# 1-Schematic_passcipher.net
KiCad netlist of a schematic drawn in EasyEDA
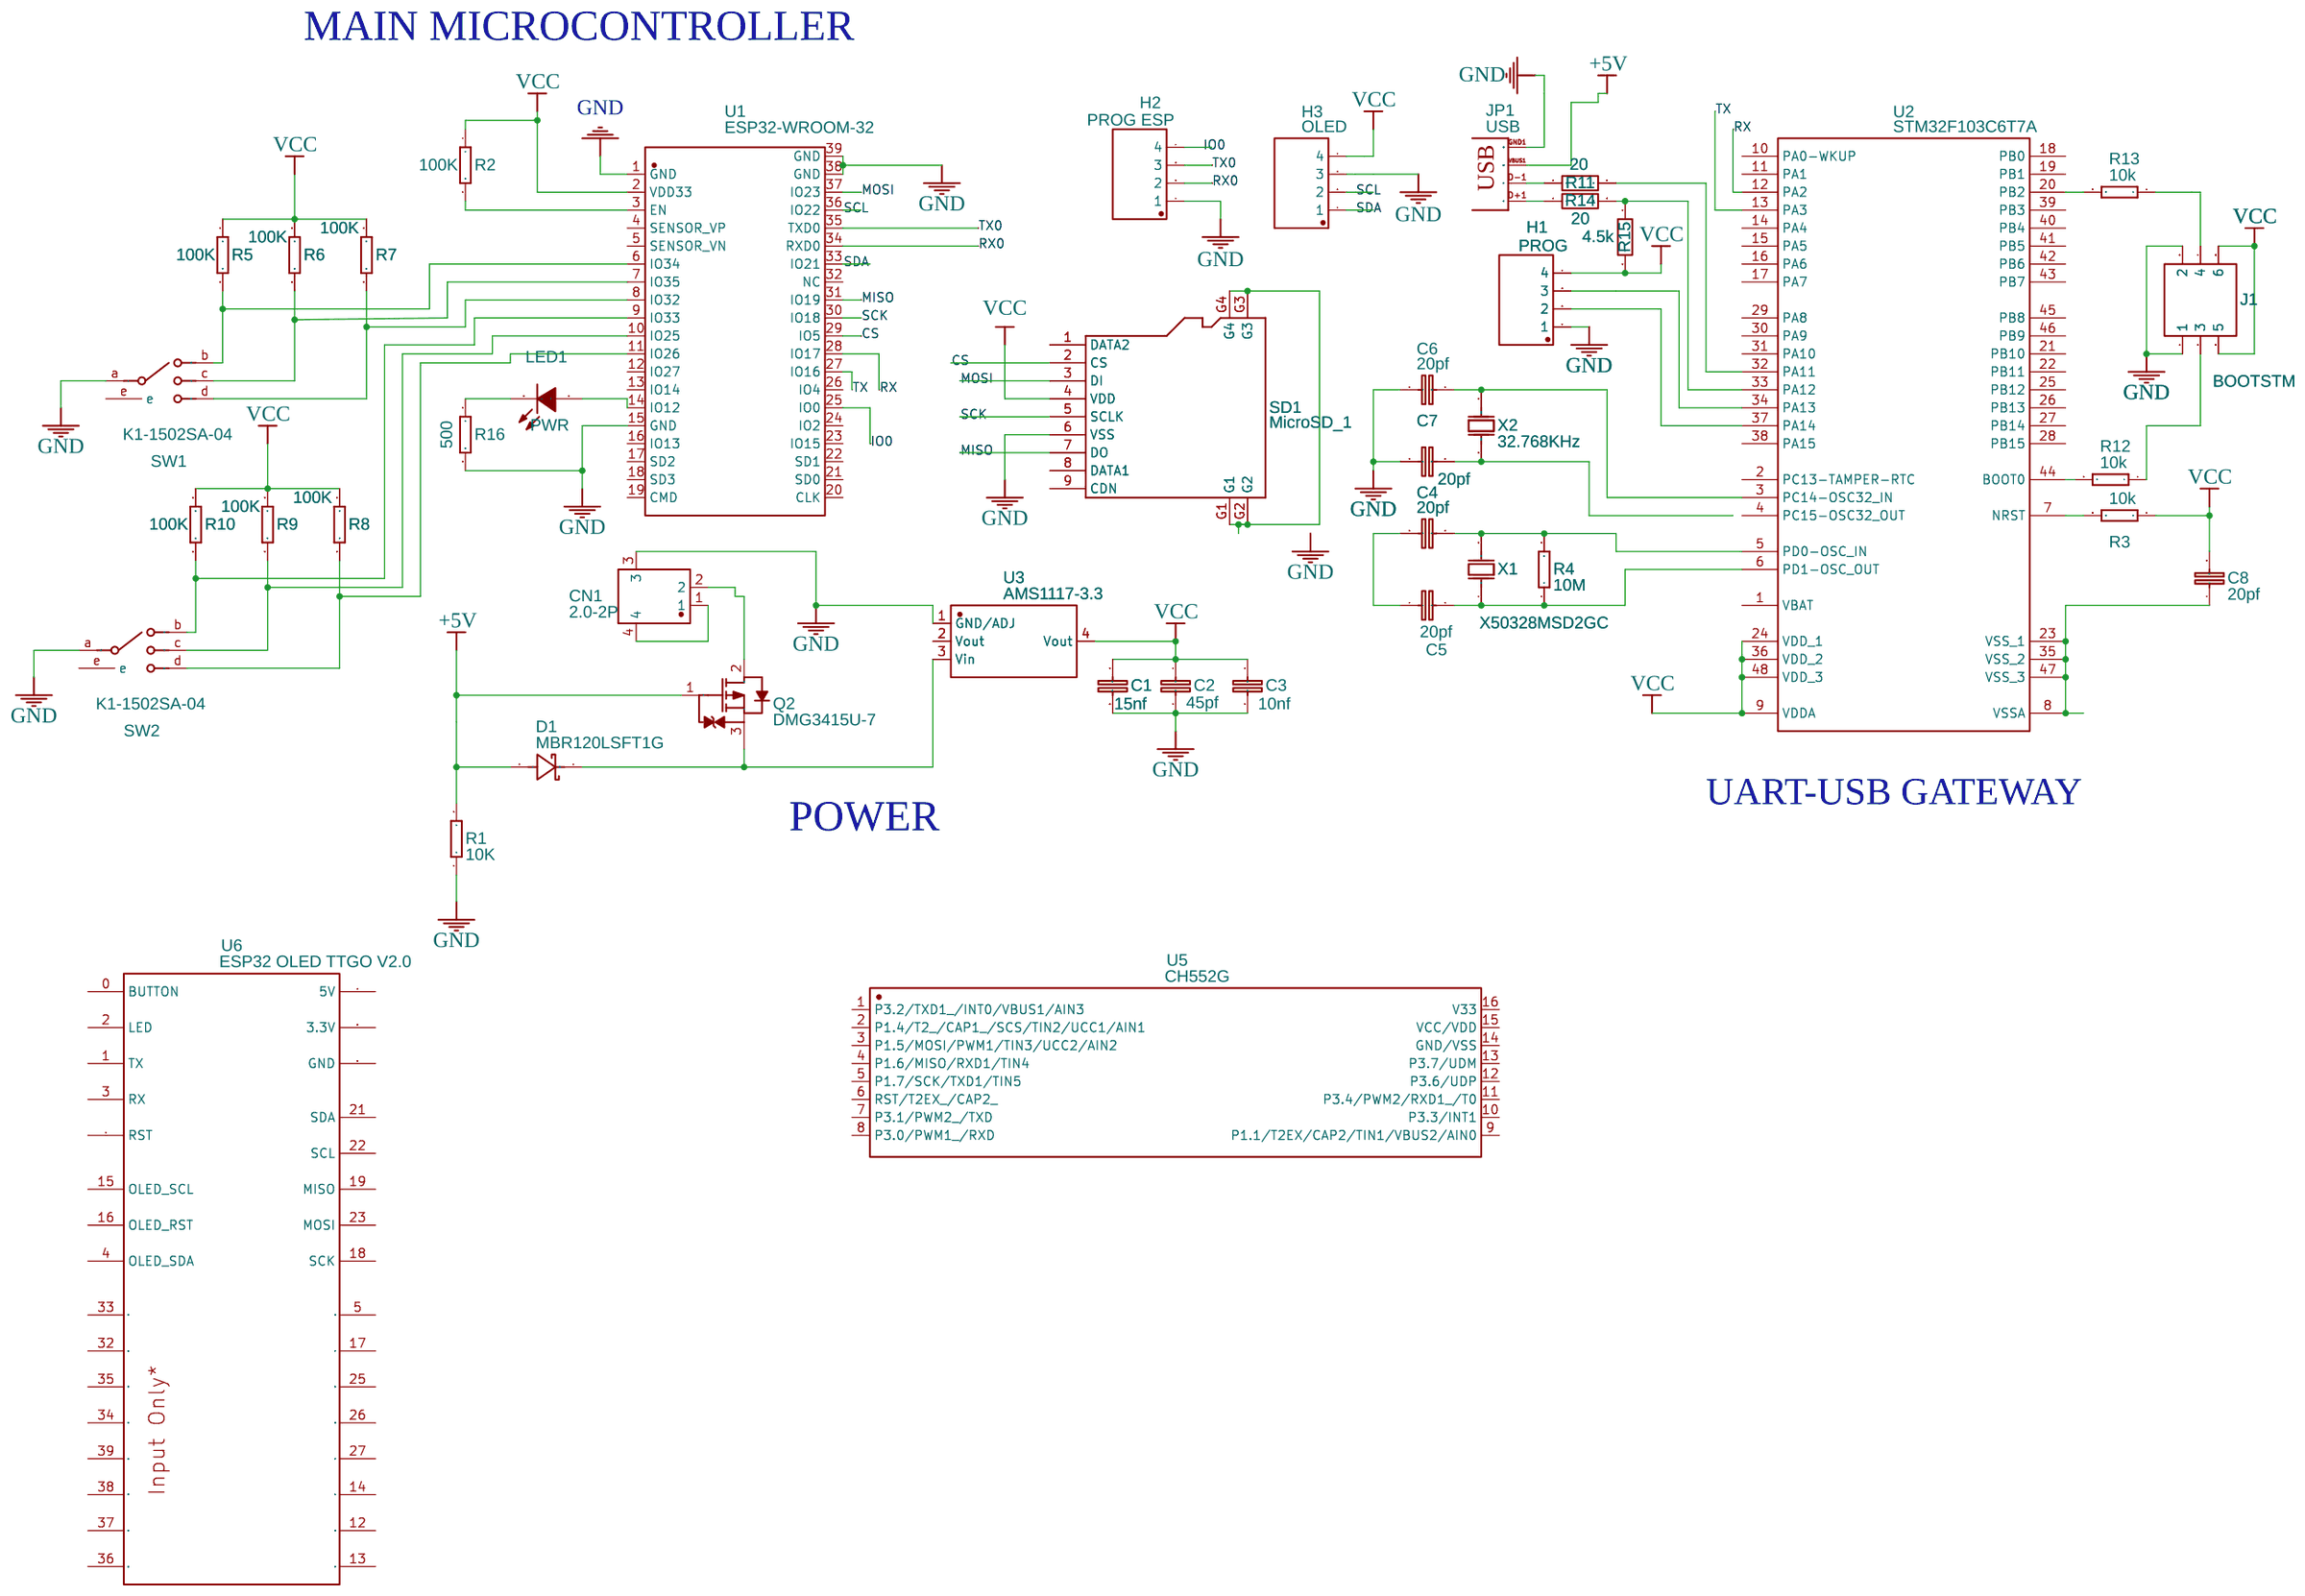
[diagram p0: Sheet_1]
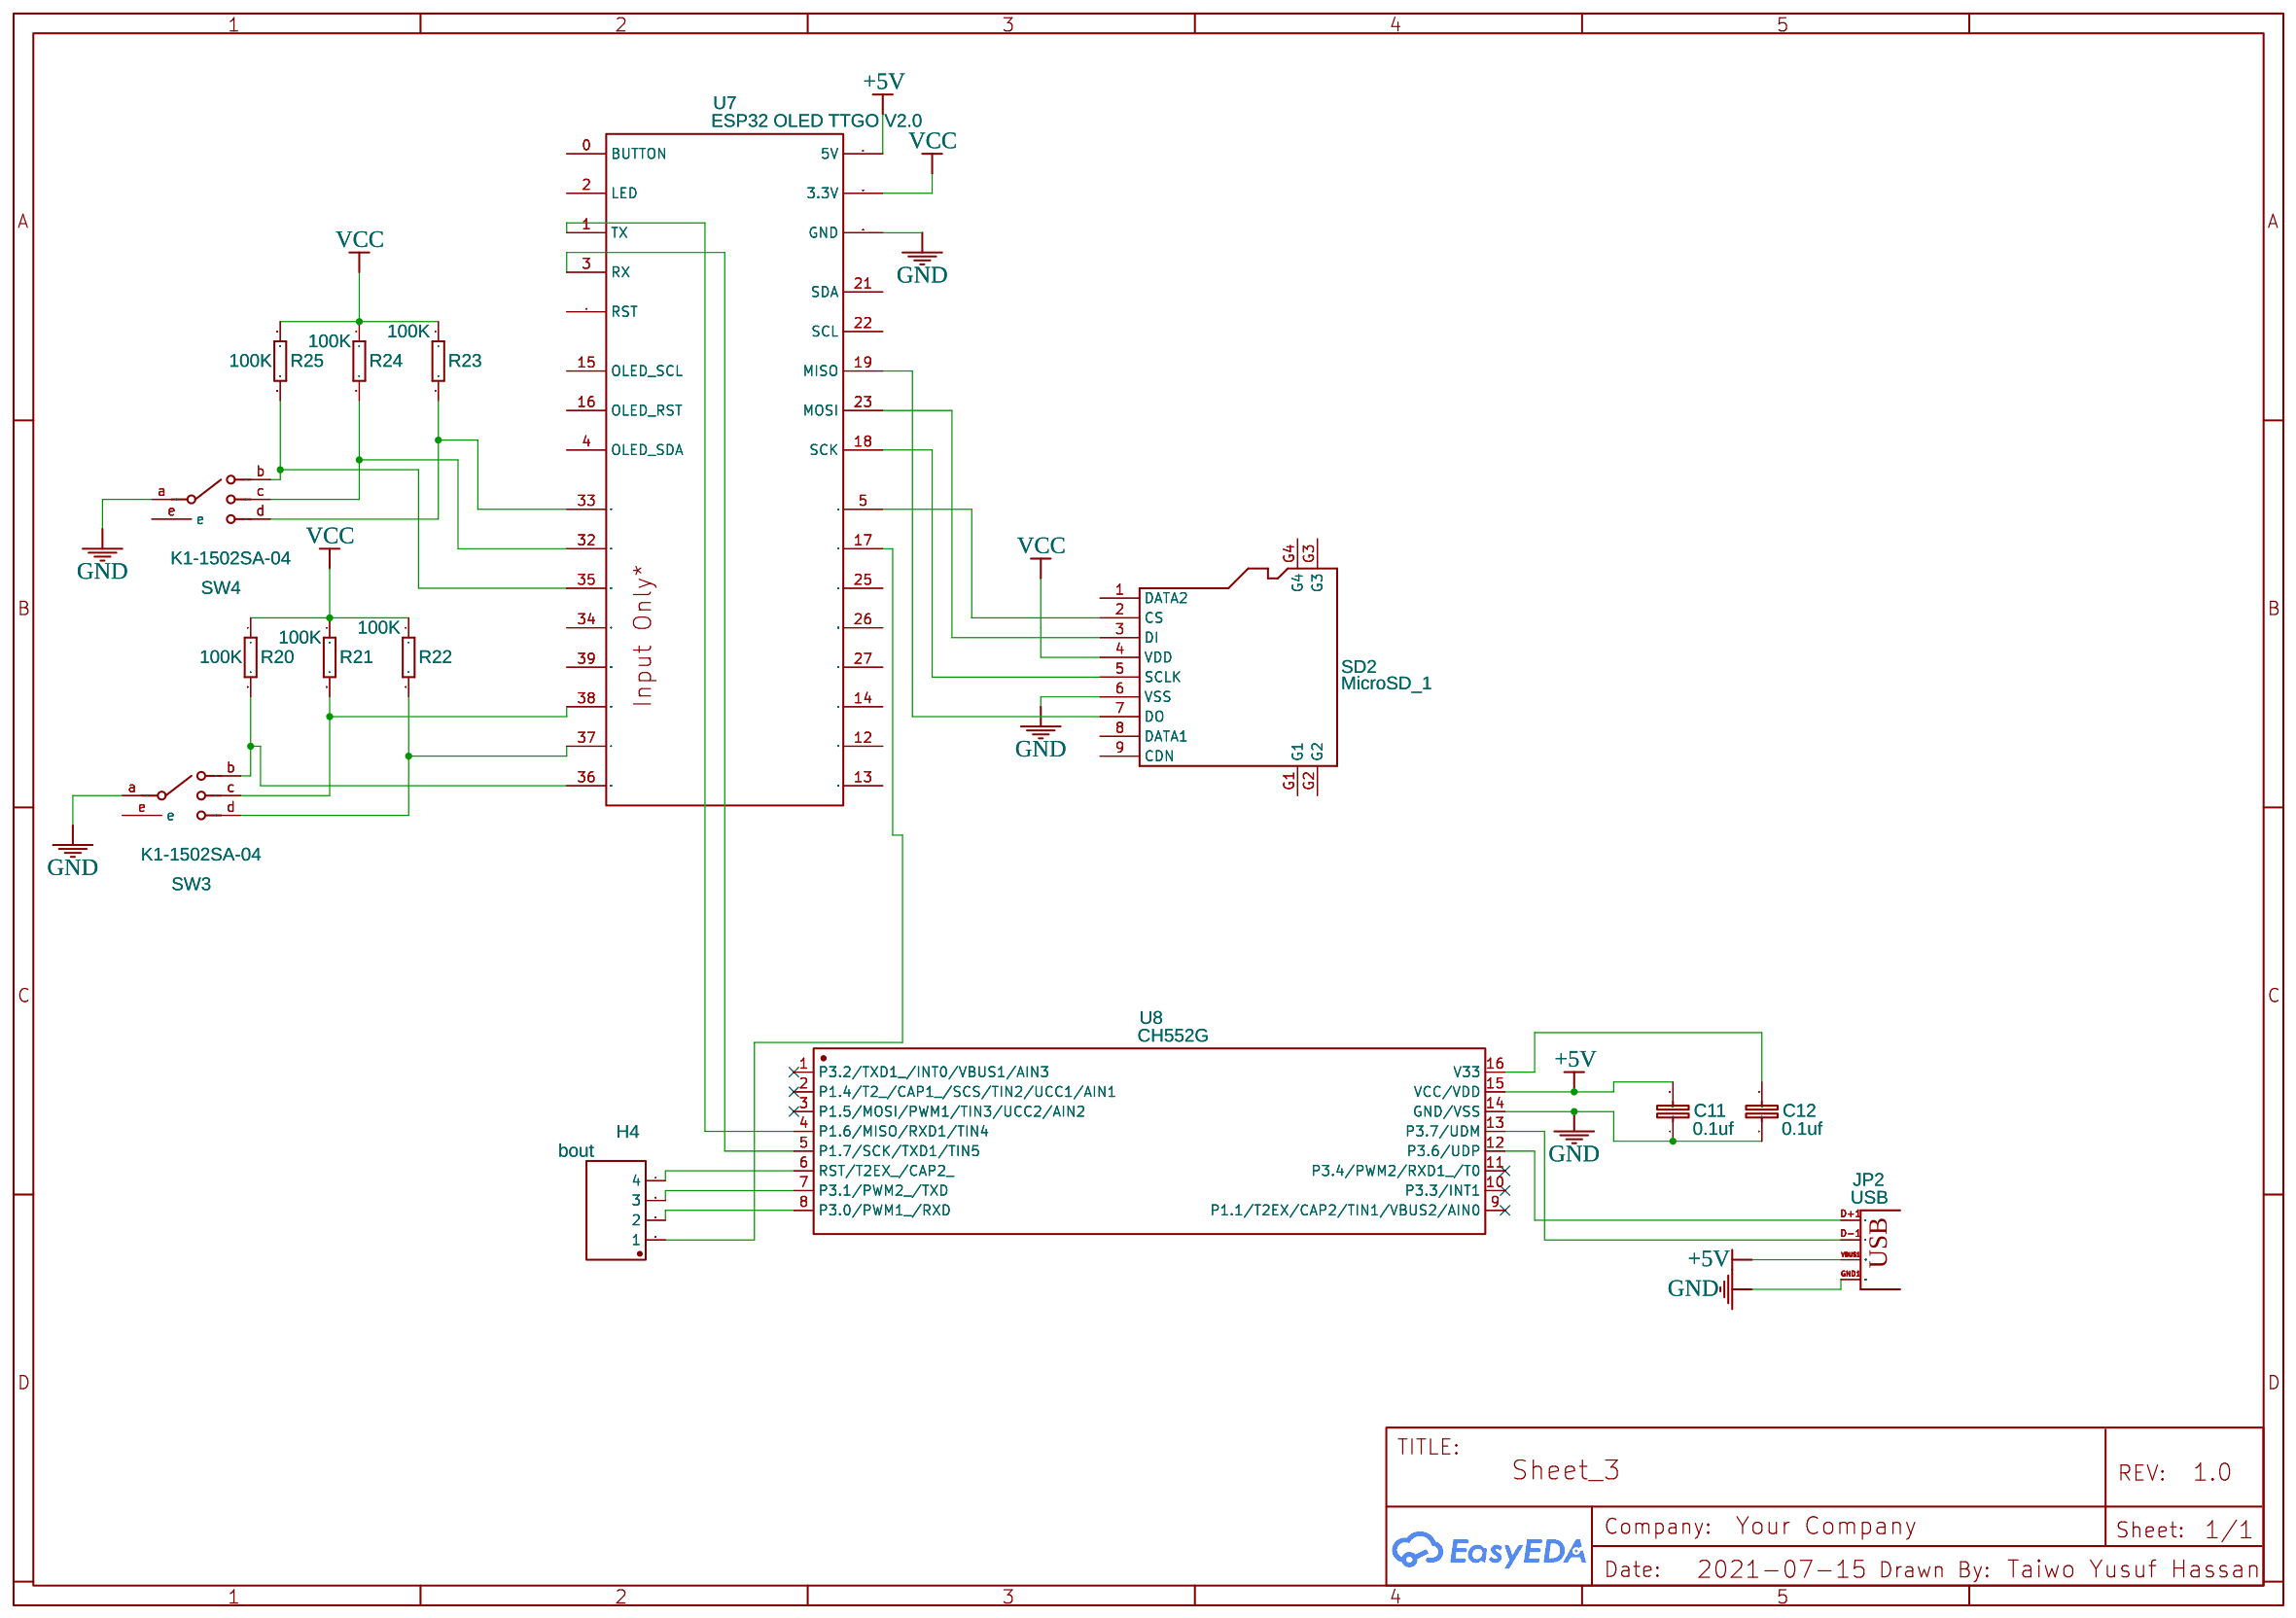
[diagram p1: expansionboard]

(export (version "E")
  (design (tool "Eeschema 10.0.6"))
  (components
    (comp (ref "C1") (value "15nf") (libsource (lib "") (part "CAPACITOR_NPOL_1")))
    (comp (ref "C2") (value "45pf") (libsource (lib "") (part "CAPACITOR_NPOL_1")))
    (comp (ref "C3") (value "10nf") (libsource (lib "") (part "CAPACITOR_NPOL_1")))
    (comp (ref "C4") (value "20pf") (libsource (lib "") (part "CAPACITOR_NPOL")))
    (comp (ref "C5") (value "20pf") (libsource (lib "") (part "CAPACITOR_NPOL")))
    (comp (ref "C6") (value "20pf") (libsource (lib "") (part "CAPACITOR_NPOL")))
    (comp (ref "C7") (value "20pf") (libsource (lib "") (part "CAPACITOR_NPOL")))
    (comp (ref "C8") (value "20pf") (libsource (lib "") (part "CAPACITOR_NPOL_2")))
    (comp (ref "CN1")
      (value "2.0-2P")
      (fields (field (name "BOM_Supplier Part") "C146053"))
      (libsource (lib "") (part "2.0-2P"))
    )
    (comp (ref "D1")
      (value "MBR120LSFT1G")
      (fields (field (name "BOM_Supplier Part") "C891416"))
      (libsource (lib "") (part "MBR120LSFT1G"))
    )
    (comp (ref "H1")
      (value "PROG")
      (fields
        (field (name "BOM_Manufacturer Part") "210S-1*4P L=11.6MMGold-plated black")
        (field (name "BOM_Supplier Part") "C124378")
      )
      (libsource (lib "") (part "Header-Male-2.54_1x4"))
    )
    (comp (ref "H2")
      (value "PROG ESP")
      (fields
        (field (name "BOM_Manufacturer Part") "210S-1*4P L=11.6MMGold-plated black")
        (field (name "BOM_Supplier Part") "C124378")
      )
      (libsource (lib "") (part "Header-Male-2.54_1x4"))
    )
    (comp (ref "H3")
      (value "OLED")
      (fields
        (field (name "BOM_Manufacturer Part") "210S-1*4P L=11.6MMGold-plated black")
        (field (name "BOM_Supplier Part") "C124378")
      )
      (libsource (lib "") (part "Header-Male-2.54_1x4"))
    )
    (comp (ref "J1")
      (value "BOOTSTM")
      (fields
        (field (name "BOM_Manufacturer Part") "Header-Male-2.54_2x3")
        (field (name "BOM_Supplier Part") "C65114")
      )
      (libsource (lib "") (part "Header-Male-2.54_2x3"))
    )
    (comp (ref "JP1") (value "USB") (libsource (lib "") (part "USB")))
    (comp (ref "LED1")
      (value "PWR")
      (fields
        (field (name "BOM_Manufacturer Part") "LTST-C193TGKT-5A")
        (field (name "BOM_Supplier Part") "C12065")
      )
      (libsource (lib "") (part "LTST-C193TGKT-5A"))
    )
    (comp (ref "Q2")
      (value "DMG3415U-7")
      (fields (field (name "BOM_Supplier Part") "C96616"))
      (libsource (lib "") (part "DMG3415U-7"))
    )
    (comp (ref "R1") (value "10K") (libsource (lib "") (part "RESISTOR_2")))
    (comp (ref "R2") (value "100K") (libsource (lib "") (part "RESISTOR_1")))
    (comp (ref "R3") (value "10k") (libsource (lib "") (part "RESISTOR")))
    (comp (ref "R4") (value "10M") (libsource (lib "") (part "RESISTOR_2")))
    (comp (ref "R5") (value "100K") (libsource (lib "") (part "RESISTOR_1")))
    (comp (ref "R6") (value "100K") (libsource (lib "") (part "RESISTOR_1")))
    (comp (ref "R7") (value "100K") (libsource (lib "") (part "RESISTOR_1")))
    (comp (ref "R8") (value "100K") (libsource (lib "") (part "RESISTOR_1")))
    (comp (ref "R9") (value "100K") (libsource (lib "") (part "RESISTOR_1")))
    (comp (ref "R10") (value "100K") (libsource (lib "") (part "RESISTOR_1")))
    (comp (ref "R11")
      (value "20")
      (fields
        (field (name "BOM_Manufacturer Part") "RS-03K3242FT")
        (field (name "BOM_Supplier Part") "C304734")
      )
      (libsource (lib "") (part "RS-03K3242FT_1"))
    )
    (comp (ref "R12") (value "10k") (libsource (lib "") (part "RESISTOR")))
    (comp (ref "R13") (value "10k") (libsource (lib "") (part "RESISTOR")))
    (comp (ref "R14")
      (value "20")
      (fields
        (field (name "BOM_Manufacturer Part") "RS-03K3242FT")
        (field (name "BOM_Supplier Part") "C304734")
      )
      (libsource (lib "") (part "RS-03K3242FT_1"))
    )
    (comp (ref "R15")
      (value "4.5k")
      (fields
        (field (name "BOM_Manufacturer Part") "RS-03K3242FT")
        (field (name "BOM_Supplier Part") "C304734")
      )
      (libsource (lib "") (part "RS-03K3242FT"))
    )
    (comp (ref "R16") (value "500") (libsource (lib "") (part "RESISTOR_1")))
    (comp (ref "SD1")
      (value "MicroSD_1")
      (fields (field (name "BOM_Manufacturer Part") "?") (field (name "BOM_Supplier Part") "320090008"))
      (libsource (lib "") (part "MicroSD_1"))
    )
    (comp (ref "SW1")
      (value "K1-1502SA-04")
      (fields (field (name "BOM_Supplier Part") "C145914"))
      (libsource (lib "") (part "K1-1502SA-04"))
    )
    (comp (ref "SW2")
      (value "K1-1502SA-04")
      (fields (field (name "BOM_Supplier Part") "C145914"))
      (libsource (lib "") (part "K1-1502SA-04"))
    )
    (comp (ref "U1")
      (value "ESP32-WROOM-32")
      (fields (field (name "BOM_Supplier Part") "C503587"))
      (libsource (lib "") (part "ESP32-WROOM-32"))
    )
    (comp (ref "U2")
      (value "STM32F103C6T7A")
      (fields (field (name "BOM_Supplier Part") "C222074"))
      (libsource (lib "") (part "STM32F103C6T7A"))
    )
    (comp (ref "U3")
      (value "AMS1117-3.3")
      (fields (field (name "BOM_Supplier Part") "C6186"))
      (libsource (lib "") (part "AMS1117-3.3"))
    )
    (comp (ref "U5")
      (value "CH552G")
      (fields (field (name "BOM_Supplier Part") "C111292"))
      (libsource (lib "") (part "CH552G"))
    )
    (comp (ref "U6")
      (value "ESP32 OLED TTGO V2.0")
      (fields
        (field (name "BOM_Manufacturer Part") "ESP32 OLED TTGO V2.0 Pro")
        (field (name "BOM_Supplier Part") "32822105291")
      )
      (libsource (lib "") (part "ESP32 OLED TTGO V2.0"))
    )
    (comp (ref "X1")
      (value "X50328MSD2GC")
      (fields (field (name "BOM_Supplier Part") "C18560"))
      (libsource (lib "") (part "X50328MSD2GC"))
    )
    (comp (ref "X2")
      (value "32.768KHz")
      (fields
        (field (name "BOM_Manufacturer Part") "9H0322LCSC-DZF2S")
        (field (name "BOM_Supplier Part") "C90943")
      )
      (libsource (lib "") (part "9H0322LCSC-DZF2S"))
    )
    (comp (ref "C11") (value "0.1uf") (libsource (lib "") (part "CAPACITOR_NPOL")))
    (comp (ref "C12") (value "0.1uf") (libsource (lib "") (part "CAPACITOR_NPOL")))
    (comp (ref "H4")
      (value "bout")
      (fields
        (field (name "BOM_Manufacturer Part") "210S-1*4P L=11.6MMGold-plated black")
        (field (name "BOM_Supplier Part") "C124378")
      )
      (libsource (lib "") (part "Header-Male-2.54_1x4"))
    )
    (comp (ref "JP2") (value "USB") (libsource (lib "") (part "USB")))
    (comp (ref "R20") (value "100K") (libsource (lib "") (part "RESISTOR")))
    (comp (ref "R21") (value "100K") (libsource (lib "") (part "RESISTOR")))
    (comp (ref "R22") (value "100K") (libsource (lib "") (part "RESISTOR")))
    (comp (ref "R23") (value "100K") (libsource (lib "") (part "RESISTOR")))
    (comp (ref "R24") (value "100K") (libsource (lib "") (part "RESISTOR")))
    (comp (ref "R25") (value "100K") (libsource (lib "") (part "RESISTOR")))
    (comp (ref "SD2")
      (value "MicroSD_1")
      (fields (field (name "BOM_Manufacturer Part") "?") (field (name "BOM_Supplier Part") "320090008"))
      (libsource (lib "") (part "MicroSD_1"))
    )
    (comp (ref "SW3")
      (value "K1-1502SA-04")
      (fields (field (name "BOM_Supplier Part") "C145914"))
      (libsource (lib "") (part "K1-1502SA-04"))
    )
    (comp (ref "SW4")
      (value "K1-1502SA-04")
      (fields (field (name "BOM_Supplier Part") "C145914"))
      (libsource (lib "") (part "K1-1502SA-04"))
    )
    (comp (ref "U7")
      (value "ESP32 OLED TTGO V2.0")
      (fields
        (field (name "BOM_Manufacturer Part") "ESP32 OLED TTGO V2.0 Pro")
        (field (name "BOM_Supplier Part") "32822105291")
      )
      (libsource (lib "") (part "ESP32 OLED TTGO V2.0"))
    )
    (comp (ref "U8")
      (value "CH552G")
      (fields (field (name "BOM_Supplier Part") "C111292"))
      (libsource (lib "") (part "CH552G"))
    )
  )
  (nets
    (net (code "1") (name "+5V") (class "Default")
      (node (ref "C11") (pin "2") (pinfunction "2_2") (pintype "unspecified"))
      (node (ref "D1") (pin "2") (pinfunction "A_2") (pintype "unspecified"))
      (node (ref "JP1") (pin "VBUS1") (pinfunction "VBUS_VBUS1") (pintype "unspecified"))
      (node (ref "JP2") (pin "VBUS1") (pinfunction "VBUS_VBUS1") (pintype "unspecified"))
      (node (ref "Q2") (pin "1") (pinfunction "G_1") (pintype "unspecified"))
      (node (ref "R1") (pin "2") (pinfunction "2_2") (pintype "unspecified"))
      (node (ref "U7") (pin "41") (pinfunction "5V_41") (pintype "unspecified"))
      (node (ref "U8") (pin "15") (pinfunction "VCC/VDD_15") (pintype "unspecified"))
    )
    (net (code "2") (name "CS") (class "Default")
      (node (ref "SD1") (pin "2") (pinfunction "CS_2") (pintype "unspecified"))
      (node (ref "U1") (pin "29") (pinfunction "IO5_29") (pintype "unspecified"))
    )
    (net (code "3") (name "GND") (class "Default")
      (node (ref "C1") (pin "2") (pinfunction "2_2") (pintype "unspecified"))
      (node (ref "C11") (pin "1") (pinfunction "1_1") (pintype "unspecified"))
      (node (ref "C12") (pin "1") (pinfunction "1_1") (pintype "unspecified"))
      (node (ref "C2") (pin "2") (pinfunction "2_2") (pintype "unspecified"))
      (node (ref "C3") (pin "2") (pinfunction "2_2") (pintype "unspecified"))
      (node (ref "C6") (pin "1") (pinfunction "1_1") (pintype "unspecified"))
      (node (ref "C7") (pin "1") (pinfunction "1_1") (pintype "unspecified"))
      (node (ref "CN1") (pin "3") (pinfunction "3_3") (pintype "unspecified"))
      (node (ref "H1") (pin "1") (pinfunction "1_1") (pintype "unspecified"))
      (node (ref "H2") (pin "1") (pinfunction "1_1") (pintype "unspecified"))
      (node (ref "H3") (pin "3") (pinfunction "3_3") (pintype "unspecified"))
      (node (ref "J1") (pin "1") (pinfunction "1_1") (pintype "input"))
      (node (ref "J1") (pin "2") (pinfunction "2_2") (pintype "input"))
      (node (ref "JP1") (pin "GND1") (pinfunction "GND_GND1") (pintype "unspecified"))
      (node (ref "JP2") (pin "GND1") (pinfunction "GND_GND1") (pintype "unspecified"))
      (node (ref "R1") (pin "1") (pinfunction "1_1") (pintype "unspecified"))
      (node (ref "R16") (pin "2") (pinfunction "2_2") (pintype "unspecified"))
      (node (ref "SD1") (pin "6") (pinfunction "VSS_6") (pintype "unspecified"))
      (node (ref "SD2") (pin "6") (pinfunction "VSS_6") (pintype "unspecified"))
      (node (ref "SW1") (pin "a") (pinfunction "a_a") (pintype "unspecified"))
      (node (ref "SW2") (pin "a") (pinfunction "a_a") (pintype "unspecified"))
      (node (ref "SW3") (pin "a") (pinfunction "a_a") (pintype "unspecified"))
      (node (ref "SW4") (pin "a") (pinfunction "a_a") (pintype "unspecified"))
      (node (ref "U1") (pin "1") (pinfunction "GND_1") (pintype "unspecified"))
      (node (ref "U1") (pin "15") (pinfunction "GND_15") (pintype "unspecified"))
      (node (ref "U1") (pin "38") (pinfunction "GND_38") (pintype "unspecified"))
      (node (ref "U1") (pin "39") (pinfunction "GND_39") (pintype "unspecified"))
      (node (ref "U3") (pin "1") (pinfunction "GND/ADJ_1") (pintype "unspecified"))
      (node (ref "U7") (pin "40") (pinfunction "GND_40") (pintype "unspecified"))
      (node (ref "U8") (pin "14") (pinfunction "GND/VSS_14") (pintype "unspecified"))
    )
    (net (code "4") (name "IO0") (class "Default")
      (node (ref "H2") (pin "4") (pinfunction "4_4") (pintype "unspecified"))
      (node (ref "U1") (pin "25") (pinfunction "IO0_25") (pintype "unspecified"))
    )
    (net (code "5") (name "MISO") (class "Default")
      (node (ref "SD1") (pin "7") (pinfunction "DO_7") (pintype "unspecified"))
      (node (ref "U1") (pin "31") (pinfunction "IO19_31") (pintype "unspecified"))
    )
    (net (code "6") (name "MOSI") (class "Default")
      (node (ref "SD1") (pin "3") (pinfunction "DI_3") (pintype "unspecified"))
      (node (ref "U1") (pin "37") (pinfunction "IO23_37") (pintype "unspecified"))
    )
    (net (code "7") (name "Net-(C4-Pad1)") (class "Default")
      (node (ref "C4") (pin "1") (pinfunction "1_1") (pintype "unspecified"))
      (node (ref "C5") (pin "1") (pinfunction "1_1") (pintype "unspecified"))
    )
    (net (code "8") (name "Net-(CN1-Pad1)") (class "Default")
      (node (ref "CN1") (pin "1") (pinfunction "1_1") (pintype "unspecified"))
      (node (ref "CN1") (pin "4") (pinfunction "4_4") (pintype "unspecified"))
    )
    (net (code "9") (name "Net-(D1-C)") (class "Default")
      (node (ref "D1") (pin "1") (pinfunction "C_1") (pintype "unspecified"))
      (node (ref "Q2") (pin "3") (pinfunction "S_3") (pintype "unspecified"))
      (node (ref "U3") (pin "3") (pinfunction "Vin_3") (pintype "unspecified"))
    )
    (net (code "10") (name "Net-(H4-Pad1)") (class "Default")
      (node (ref "H4") (pin "1") (pinfunction "1_1") (pintype "unspecified"))
      (node (ref "U7") (pin "17") (pinfunction "17_17") (pintype "unspecified"))
    )
    (net (code "11") (name "Net-(J1-Pad3)") (class "Default")
      (node (ref "J1") (pin "3") (pinfunction "3_3") (pintype "input"))
      (node (ref "R12") (pin "1") (pinfunction "1_1") (pintype "unspecified"))
    )
    (net (code "12") (name "Net-(J1-Pad4)") (class "Default")
      (node (ref "J1") (pin "4") (pinfunction "4_4") (pintype "input"))
      (node (ref "R13") (pin "1") (pinfunction "1_1") (pintype "unspecified"))
    )
    (net (code "13") (name "Net-(JP1-D+)") (class "Default")
      (node (ref "JP1") (pin "D+1") (pinfunction "D+_D+1") (pintype "unspecified"))
      (node (ref "R14") (pin "1") (pinfunction "1_1") (pintype "unspecified"))
    )
    (net (code "14") (name "Net-(JP1-D-)") (class "Default")
      (node (ref "JP1") (pin "D-1") (pinfunction "D-_D-1") (pintype "unspecified"))
      (node (ref "R11") (pin "1") (pinfunction "1_1") (pintype "unspecified"))
    )
    (net (code "15") (name "Net-(JP2-D+)") (class "Default")
      (node (ref "JP2") (pin "D+1") (pinfunction "D+_D+1") (pintype "unspecified"))
      (node (ref "U8") (pin "12") (pinfunction "P3.6/UDP_12") (pintype "unspecified"))
    )
    (net (code "16") (name "Net-(JP2-D-)") (class "Default")
      (node (ref "JP2") (pin "D-1") (pinfunction "D-_D-1") (pintype "unspecified"))
      (node (ref "U8") (pin "13") (pinfunction "P3.7/UDM_13") (pintype "unspecified"))
    )
    (net (code "17") (name "Net-(LED1-A)") (class "Default")
      (node (ref "LED1") (pin "1") (pinfunction "A_1") (pintype "unspecified"))
      (node (ref "U1") (pin "14") (pinfunction "IO12_14") (pintype "unspecified"))
    )
    (net (code "18") (name "Net-(LED1-K)") (class "Default")
      (node (ref "LED1") (pin "2") (pinfunction "K_2") (pintype "unspecified"))
      (node (ref "R16") (pin "1") (pinfunction "1_1") (pintype "unspecified"))
    )
    (net (code "19") (name "Net-(Q2-D)") (class "Default")
      (node (ref "CN1") (pin "2") (pinfunction "2_2") (pintype "unspecified"))
      (node (ref "Q2") (pin "2") (pinfunction "D_2") (pintype "unspecified"))
    )
    (net (code "20") (name "Net-(R20-Pad2)") (class "Default")
      (node (ref "R20") (pin "2") (pinfunction "2_2") (pintype "unspecified"))
      (node (ref "SW3") (pin "b") (pinfunction "b_b") (pintype "unspecified"))
      (node (ref "U7") (pin "36") (pinfunction "36_36") (pintype "unspecified"))
    )
    (net (code "21") (name "Net-(R21-Pad2)") (class "Default")
      (node (ref "R21") (pin "2") (pinfunction "2_2") (pintype "unspecified"))
      (node (ref "SW3") (pin "c") (pinfunction "c_c") (pintype "unspecified"))
      (node (ref "U7") (pin "38") (pinfunction "38_38") (pintype "unspecified"))
    )
    (net (code "22") (name "Net-(R22-Pad2)") (class "Default")
      (node (ref "R22") (pin "2") (pinfunction "2_2") (pintype "unspecified"))
      (node (ref "SW3") (pin "d") (pinfunction "d_d") (pintype "unspecified"))
      (node (ref "U7") (pin "37") (pinfunction "37_37") (pintype "unspecified"))
    )
    (net (code "23") (name "Net-(R23-Pad2)") (class "Default")
      (node (ref "R23") (pin "2") (pinfunction "2_2") (pintype "unspecified"))
      (node (ref "SW4") (pin "d") (pinfunction "d_d") (pintype "unspecified"))
      (node (ref "U7") (pin "33") (pinfunction "33_33") (pintype "unspecified"))
    )
    (net (code "24") (name "Net-(R24-Pad2)") (class "Default")
      (node (ref "R24") (pin "2") (pinfunction "2_2") (pintype "unspecified"))
      (node (ref "SW4") (pin "c") (pinfunction "c_c") (pintype "unspecified"))
      (node (ref "U7") (pin "32") (pinfunction "32_32") (pintype "unspecified"))
    )
    (net (code "25") (name "Net-(R25-Pad2)") (class "Default")
      (node (ref "R25") (pin "2") (pinfunction "2_2") (pintype "unspecified"))
      (node (ref "SW4") (pin "b") (pinfunction "b_b") (pintype "unspecified"))
      (node (ref "U7") (pin "35") (pinfunction "35_35") (pintype "unspecified"))
    )
    (net (code "26") (name "Net-(SD1-PadG1)") (class "Default")
      (node (ref "SD1") (pin "G1") (pinfunction "G1_G1") (pintype "unspecified"))
      (node (ref "SD1") (pin "G2") (pinfunction "G2_G2") (pintype "unspecified"))
      (node (ref "SD1") (pin "G3") (pinfunction "G3_G3") (pintype "unspecified"))
      (node (ref "SD1") (pin "G4") (pinfunction "G4_G4") (pintype "unspecified"))
    )
    (net (code "27") (name "Net-(SD2-CS)") (class "Default")
      (node (ref "SD2") (pin "2") (pinfunction "CS_2") (pintype "unspecified"))
      (node (ref "U7") (pin "5") (pinfunction "5_5") (pintype "unspecified"))
    )
    (net (code "28") (name "Net-(SD2-DI)") (class "Default")
      (node (ref "SD2") (pin "3") (pinfunction "DI_3") (pintype "unspecified"))
      (node (ref "U7") (pin "23") (pinfunction "MOSI_23") (pintype "unspecified"))
    )
    (net (code "29") (name "Net-(SD2-DO)") (class "Default")
      (node (ref "SD2") (pin "7") (pinfunction "DO_7") (pintype "unspecified"))
      (node (ref "U7") (pin "19") (pinfunction "MISO_19") (pintype "unspecified"))
    )
    (net (code "30") (name "Net-(SD2-SCLK)") (class "Default")
      (node (ref "SD2") (pin "5") (pinfunction "SCLK_5") (pintype "unspecified"))
      (node (ref "U7") (pin "18") (pinfunction "SCK_18") (pintype "unspecified"))
    )
    (net (code "31") (name "Net-(U1-EN)") (class "Default")
      (node (ref "R2") (pin "2") (pinfunction "2_2") (pintype "unspecified"))
      (node (ref "U1") (pin "3") (pinfunction "EN_3") (pintype "unspecified"))
    )
    (net (code "32") (name "Net-(U1-IO25)") (class "Default")
      (node (ref "R9") (pin "2") (pinfunction "2_2") (pintype "unspecified"))
      (node (ref "SW2") (pin "c") (pinfunction "c_c") (pintype "unspecified"))
      (node (ref "U1") (pin "10") (pinfunction "IO25_10") (pintype "unspecified"))
    )
    (net (code "33") (name "Net-(U1-IO26)") (class "Default")
      (node (ref "R8") (pin "2") (pinfunction "2_2") (pintype "unspecified"))
      (node (ref "SW2") (pin "d") (pinfunction "d_d") (pintype "unspecified"))
      (node (ref "U1") (pin "11") (pinfunction "IO26_11") (pintype "unspecified"))
    )
    (net (code "34") (name "Net-(U1-IO32)") (class "Default")
      (node (ref "R7") (pin "2") (pinfunction "2_2") (pintype "unspecified"))
      (node (ref "SW1") (pin "d") (pinfunction "d_d") (pintype "unspecified"))
      (node (ref "U1") (pin "8") (pinfunction "IO32_8") (pintype "unspecified"))
    )
    (net (code "35") (name "Net-(U1-IO33)") (class "Default")
      (node (ref "R10") (pin "2") (pinfunction "2_2") (pintype "unspecified"))
      (node (ref "SW2") (pin "b") (pinfunction "b_b") (pintype "unspecified"))
      (node (ref "U1") (pin "9") (pinfunction "IO33_9") (pintype "unspecified"))
    )
    (net (code "36") (name "Net-(U1-IO34)") (class "Default")
      (node (ref "R5") (pin "2") (pinfunction "2_2") (pintype "unspecified"))
      (node (ref "SW1") (pin "b") (pinfunction "b_b") (pintype "unspecified"))
      (node (ref "U1") (pin "6") (pinfunction "IO34_6") (pintype "unspecified"))
    )
    (net (code "37") (name "Net-(U1-IO35)") (class "Default")
      (node (ref "R6") (pin "2") (pinfunction "2_2") (pintype "unspecified"))
      (node (ref "SW1") (pin "c") (pinfunction "c_c") (pintype "unspecified"))
      (node (ref "U1") (pin "7") (pinfunction "IO35_7") (pintype "unspecified"))
    )
    (net (code "38") (name "Net-(U2-BOOT0)") (class "Default")
      (node (ref "R12") (pin "2") (pinfunction "2_2") (pintype "unspecified"))
      (node (ref "U2") (pin "44") (pinfunction "BOOT0_44") (pintype "unspecified"))
    )
    (net (code "39") (name "Net-(U2-NRST)") (class "Default")
      (node (ref "R3") (pin "2") (pinfunction "2_2") (pintype "unspecified"))
      (node (ref "U2") (pin "7") (pinfunction "NRST_7") (pintype "bidirectional"))
    )
    (net (code "40") (name "Net-(U2-PA11)") (class "Default")
      (node (ref "R11") (pin "2") (pinfunction "2_2") (pintype "unspecified"))
      (node (ref "U2") (pin "32") (pinfunction "PA11_32") (pintype "bidirectional"))
    )
    (net (code "41") (name "Net-(U2-PA12)") (class "Default")
      (node (ref "R14") (pin "2") (pinfunction "2_2") (pintype "unspecified"))
      (node (ref "R15") (pin "1") (pinfunction "1_1") (pintype "unspecified"))
      (node (ref "U2") (pin "33") (pinfunction "PA12_33") (pintype "bidirectional"))
    )
    (net (code "42") (name "Net-(U2-PA13)") (class "Default")
      (node (ref "H1") (pin "3") (pinfunction "3_3") (pintype "unspecified"))
      (node (ref "U2") (pin "34") (pinfunction "PA13_34") (pintype "bidirectional"))
    )
    (net (code "43") (name "Net-(U2-PA14)") (class "Default")
      (node (ref "H1") (pin "2") (pinfunction "2_2") (pintype "unspecified"))
      (node (ref "U2") (pin "37") (pinfunction "PA14_37") (pintype "bidirectional"))
    )
    (net (code "44") (name "Net-(U2-PB2)") (class "Default")
      (node (ref "R13") (pin "2") (pinfunction "2_2") (pintype "unspecified"))
      (node (ref "U2") (pin "20") (pinfunction "PB2_20") (pintype "bidirectional"))
    )
    (net (code "45") (name "Net-(U2-PC14-OSC32_IN)") (class "Default")
      (node (ref "C6") (pin "2") (pinfunction "2_2") (pintype "unspecified"))
      (node (ref "U2") (pin "3") (pinfunction "PC14-OSC32_IN_3") (pintype "bidirectional"))
      (node (ref "X2") (pin "1") (pinfunction "OSC1_1") (pintype "input"))
    )
    (net (code "46") (name "Net-(U2-PD0-OSC_IN)") (class "Default")
      (node (ref "C4") (pin "2") (pinfunction "2_2") (pintype "unspecified"))
      (node (ref "R4") (pin "2") (pinfunction "2_2") (pintype "unspecified"))
      (node (ref "U2") (pin "5") (pinfunction "PD0-OSC_IN_5") (pintype "bidirectional"))
      (node (ref "X1") (pin "2") (pinfunction "OSC2_2") (pintype "input"))
    )
    (net (code "47") (name "Net-(U2-PD1-OSC_OUT)") (class "Default")
      (node (ref "C5") (pin "2") (pinfunction "2_2") (pintype "unspecified"))
      (node (ref "R4") (pin "1") (pinfunction "1_1") (pintype "unspecified"))
      (node (ref "U2") (pin "6") (pinfunction "PD1-OSC_OUT_6") (pintype "bidirectional"))
      (node (ref "X1") (pin "1") (pinfunction "OSC1_1") (pintype "input"))
    )
    (net (code "48") (name "Net-(U2-VSSA)") (class "Default")
      (node (ref "C8") (pin "1") (pinfunction "1_1") (pintype "unspecified"))
      (node (ref "U2") (pin "23") (pinfunction "VSS_1_23") (pintype "passive"))
      (node (ref "U2") (pin "35") (pinfunction "VSS_2_35") (pintype "passive"))
      (node (ref "U2") (pin "47") (pinfunction "VSS_3_47") (pintype "passive"))
      (node (ref "U2") (pin "8") (pinfunction "VSSA_8") (pintype "passive"))
    )
    (net (code "49") (name "Net-(U7-RX)") (class "Default")
      (node (ref "U7") (pin "3") (pinfunction "RX_3") (pintype "unspecified"))
      (node (ref "U8") (pin "5") (pinfunction "P1.7/SCK/TXD1/TIN5_5") (pintype "unspecified"))
    )
    (net (code "50") (name "Net-(U7-TX)") (class "Default")
      (node (ref "U7") (pin "1") (pinfunction "TX_1") (pintype "unspecified"))
      (node (ref "U8") (pin "4") (pinfunction "P1.6/MISO/RXD1/TIN4_4") (pintype "unspecified"))
    )
    (net (code "51") (name "Net-(U8-P3.0{slash}PWM1_{slash}RXD)") (class "Default")
      (node (ref "H4") (pin "2") (pinfunction "2_2") (pintype "unspecified"))
      (node (ref "U8") (pin "8") (pinfunction "P3.0/PWM1_/RXD_8") (pintype "unspecified"))
    )
    (net (code "52") (name "Net-(U8-P3.1{slash}PWM2_{slash}TXD)") (class "Default")
      (node (ref "H4") (pin "3") (pinfunction "3_3") (pintype "unspecified"))
      (node (ref "U8") (pin "7") (pinfunction "P3.1/PWM2_/TXD_7") (pintype "unspecified"))
    )
    (net (code "53") (name "Net-(U8-RST{slash}T2EX_{slash}CAP2_)") (class "Default")
      (node (ref "H4") (pin "4") (pinfunction "4_4") (pintype "unspecified"))
      (node (ref "U8") (pin "6") (pinfunction "RST/T2EX_/CAP2__6") (pintype "unspecified"))
    )
    (net (code "54") (name "Net-(U8-V33)") (class "Default")
      (node (ref "C12") (pin "2") (pinfunction "2_2") (pintype "unspecified"))
      (node (ref "U8") (pin "16") (pinfunction "V33_16") (pintype "unspecified"))
    )
    (net (code "55") (name "Net-(X2-OSC2)") (class "Default")
      (node (ref "C7") (pin "2") (pinfunction "2_2") (pintype "unspecified"))
      (node (ref "X2") (pin "2") (pinfunction "OSC2_2") (pintype "input"))
    )
    (net (code "56") (name "RX") (class "Default")
      (node (ref "U1") (pin "28") (pinfunction "IO17_28") (pintype "unspecified"))
      (node (ref "U2") (pin "12") (pinfunction "PA2_12") (pintype "bidirectional"))
    )
    (net (code "57") (name "RX0") (class "Default")
      (node (ref "H2") (pin "2") (pinfunction "2_2") (pintype "unspecified"))
      (node (ref "U1") (pin "34") (pinfunction "RXD0_34") (pintype "unspecified"))
    )
    (net (code "58") (name "SCK") (class "Default")
      (node (ref "SD1") (pin "5") (pinfunction "SCLK_5") (pintype "unspecified"))
      (node (ref "U1") (pin "30") (pinfunction "IO18_30") (pintype "unspecified"))
    )
    (net (code "59") (name "SCL") (class "Default")
      (node (ref "H3") (pin "2") (pinfunction "2_2") (pintype "unspecified"))
      (node (ref "U1") (pin "36") (pinfunction "IO22_36") (pintype "unspecified"))
    )
    (net (code "60") (name "SDA") (class "Default")
      (node (ref "H3") (pin "1") (pinfunction "1_1") (pintype "unspecified"))
      (node (ref "U1") (pin "33") (pinfunction "IO21_33") (pintype "unspecified"))
    )
    (net (code "61") (name "TX") (class "Default")
      (node (ref "U1") (pin "27") (pinfunction "IO16_27") (pintype "unspecified"))
      (node (ref "U2") (pin "13") (pinfunction "PA3_13") (pintype "bidirectional"))
    )
    (net (code "62") (name "TX0") (class "Default")
      (node (ref "H2") (pin "3") (pinfunction "3_3") (pintype "unspecified"))
      (node (ref "U1") (pin "35") (pinfunction "TXD0_35") (pintype "unspecified"))
    )
    (net (code "63") (name "VCC") (class "Default")
      (node (ref "C1") (pin "1") (pinfunction "1_1") (pintype "unspecified"))
      (node (ref "C2") (pin "1") (pinfunction "1_1") (pintype "unspecified"))
      (node (ref "C3") (pin "1") (pinfunction "1_1") (pintype "unspecified"))
      (node (ref "C8") (pin "2") (pinfunction "2_2") (pintype "unspecified"))
      (node (ref "H1") (pin "4") (pinfunction "4_4") (pintype "unspecified"))
      (node (ref "H3") (pin "4") (pinfunction "4_4") (pintype "unspecified"))
      (node (ref "J1") (pin "5") (pinfunction "5_5") (pintype "input"))
      (node (ref "J1") (pin "6") (pinfunction "6_6") (pintype "input"))
      (node (ref "R10") (pin "1") (pinfunction "1_1") (pintype "unspecified"))
      (node (ref "R15") (pin "2") (pinfunction "2_2") (pintype "unspecified"))
      (node (ref "R2") (pin "1") (pinfunction "1_1") (pintype "unspecified"))
      (node (ref "R20") (pin "1") (pinfunction "1_1") (pintype "unspecified"))
      (node (ref "R21") (pin "1") (pinfunction "1_1") (pintype "unspecified"))
      (node (ref "R22") (pin "1") (pinfunction "1_1") (pintype "unspecified"))
      (node (ref "R23") (pin "1") (pinfunction "1_1") (pintype "unspecified"))
      (node (ref "R24") (pin "1") (pinfunction "1_1") (pintype "unspecified"))
      (node (ref "R25") (pin "1") (pinfunction "1_1") (pintype "unspecified"))
      (node (ref "R3") (pin "1") (pinfunction "1_1") (pintype "unspecified"))
      (node (ref "R5") (pin "1") (pinfunction "1_1") (pintype "unspecified"))
      (node (ref "R6") (pin "1") (pinfunction "1_1") (pintype "unspecified"))
      (node (ref "R7") (pin "1") (pinfunction "1_1") (pintype "unspecified"))
      (node (ref "R8") (pin "1") (pinfunction "1_1") (pintype "unspecified"))
      (node (ref "R9") (pin "1") (pinfunction "1_1") (pintype "unspecified"))
      (node (ref "SD1") (pin "4") (pinfunction "VDD_4") (pintype "unspecified"))
      (node (ref "SD2") (pin "4") (pinfunction "VDD_4") (pintype "unspecified"))
      (node (ref "U1") (pin "2") (pinfunction "VDD33_2") (pintype "unspecified"))
      (node (ref "U2") (pin "24") (pinfunction "VDD_1_24") (pintype "passive"))
      (node (ref "U2") (pin "36") (pinfunction "VDD_2_36") (pintype "passive"))
      (node (ref "U2") (pin "48") (pinfunction "VDD_3_48") (pintype "passive"))
      (node (ref "U2") (pin "9") (pinfunction "VDDA_9") (pintype "passive"))
      (node (ref "U3") (pin "4") (pinfunction "Vout_4") (pintype "unspecified"))
      (node (ref "U7") (pin "42") (pinfunction "3.3V_42") (pintype "unspecified"))
    )
    (net (code "64") (name "unconnected-(SD1-CDN-Pad9)") (class "Default")
      (node (ref "SD1") (pin "9") (pinfunction "CDN_9") (pintype "unspecified"))
    )
    (net (code "65") (name "unconnected-(SD1-DATA1-Pad8)") (class "Default")
      (node (ref "SD1") (pin "8") (pinfunction "DATA1_8") (pintype "unspecified"))
    )
    (net (code "66") (name "unconnected-(SD1-DATA2-Pad1)") (class "Default")
      (node (ref "SD1") (pin "1") (pinfunction "DATA2_1") (pintype "unspecified"))
    )
    (net (code "67") (name "unconnected-(SD2-CDN-Pad9)") (class "Default")
      (node (ref "SD2") (pin "9") (pinfunction "CDN_9") (pintype "unspecified"))
    )
    (net (code "68") (name "unconnected-(SD2-DATA1-Pad8)") (class "Default")
      (node (ref "SD2") (pin "8") (pinfunction "DATA1_8") (pintype "unspecified"))
    )
    (net (code "69") (name "unconnected-(SD2-DATA2-Pad1)") (class "Default")
      (node (ref "SD2") (pin "1") (pinfunction "DATA2_1") (pintype "unspecified"))
    )
    (net (code "70") (name "unconnected-(SD2-PadG1)") (class "Default")
      (node (ref "SD2") (pin "G1") (pinfunction "G1_G1") (pintype "unspecified"))
    )
    (net (code "71") (name "unconnected-(SD2-PadG2)") (class "Default")
      (node (ref "SD2") (pin "G2") (pinfunction "G2_G2") (pintype "unspecified"))
    )
    (net (code "72") (name "unconnected-(SD2-PadG3)") (class "Default")
      (node (ref "SD2") (pin "G3") (pinfunction "G3_G3") (pintype "unspecified"))
    )
    (net (code "73") (name "unconnected-(SD2-PadG4)") (class "Default")
      (node (ref "SD2") (pin "G4") (pinfunction "G4_G4") (pintype "unspecified"))
    )
    (net (code "74") (name "unconnected-(SW1-Pade)") (class "Default")
      (node (ref "SW1") (pin "e") (pinfunction "e_e") (pintype "unspecified"))
    )
    (net (code "75") (name "unconnected-(SW2-Pade)") (class "Default")
      (node (ref "SW2") (pin "e") (pinfunction "e_e") (pintype "unspecified"))
    )
    (net (code "76") (name "unconnected-(SW3-Pade)") (class "Default")
      (node (ref "SW3") (pin "e") (pinfunction "e_e") (pintype "unspecified"))
    )
    (net (code "77") (name "unconnected-(SW4-Pade)") (class "Default")
      (node (ref "SW4") (pin "e") (pinfunction "e_e") (pintype "unspecified"))
    )
    (net (code "78") (name "unconnected-(U1-CLK-Pad20)") (class "Default")
      (node (ref "U1") (pin "20") (pinfunction "CLK_20") (pintype "unspecified"))
    )
    (net (code "79") (name "unconnected-(U1-CMD-Pad19)") (class "Default")
      (node (ref "U1") (pin "19") (pinfunction "CMD_19") (pintype "unspecified"))
    )
    (net (code "80") (name "unconnected-(U1-IO2-Pad24)") (class "Default")
      (node (ref "U1") (pin "24") (pinfunction "IO2_24") (pintype "unspecified"))
    )
    (net (code "81") (name "unconnected-(U1-IO4-Pad26)") (class "Default")
      (node (ref "U1") (pin "26") (pinfunction "IO4_26") (pintype "unspecified"))
    )
    (net (code "82") (name "unconnected-(U1-IO13-Pad16)") (class "Default")
      (node (ref "U1") (pin "16") (pinfunction "IO13_16") (pintype "unspecified"))
    )
    (net (code "83") (name "unconnected-(U1-IO14-Pad13)") (class "Default")
      (node (ref "U1") (pin "13") (pinfunction "IO14_13") (pintype "unspecified"))
    )
    (net (code "84") (name "unconnected-(U1-IO15-Pad23)") (class "Default")
      (node (ref "U1") (pin "23") (pinfunction "IO15_23") (pintype "unspecified"))
    )
    (net (code "85") (name "unconnected-(U1-IO27-Pad12)") (class "Default")
      (node (ref "U1") (pin "12") (pinfunction "IO27_12") (pintype "unspecified"))
    )
    (net (code "86") (name "unconnected-(U1-NC-Pad32)") (class "Default")
      (node (ref "U1") (pin "32") (pinfunction "NC_32") (pintype "unspecified"))
    )
    (net (code "87") (name "unconnected-(U1-SD0-Pad21)") (class "Default")
      (node (ref "U1") (pin "21") (pinfunction "SD0_21") (pintype "unspecified"))
    )
    (net (code "88") (name "unconnected-(U1-SD1-Pad22)") (class "Default")
      (node (ref "U1") (pin "22") (pinfunction "SD1_22") (pintype "unspecified"))
    )
    (net (code "89") (name "unconnected-(U1-SD2-Pad17)") (class "Default")
      (node (ref "U1") (pin "17") (pinfunction "SD2_17") (pintype "unspecified"))
    )
    (net (code "90") (name "unconnected-(U1-SD3-Pad18)") (class "Default")
      (node (ref "U1") (pin "18") (pinfunction "SD3_18") (pintype "unspecified"))
    )
    (net (code "91") (name "unconnected-(U1-SENSOR_VN-Pad5)") (class "Default")
      (node (ref "U1") (pin "5") (pinfunction "SENSOR_VN_5") (pintype "unspecified"))
    )
    (net (code "92") (name "unconnected-(U1-SENSOR_VP-Pad4)") (class "Default")
      (node (ref "U1") (pin "4") (pinfunction "SENSOR_VP_4") (pintype "unspecified"))
    )
    (net (code "93") (name "unconnected-(U2-PA0-WKUP-Pad10)") (class "Default")
      (node (ref "U2") (pin "10") (pinfunction "PA0-WKUP_10") (pintype "bidirectional"))
    )
    (net (code "94") (name "unconnected-(U2-PA1-Pad11)") (class "Default")
      (node (ref "U2") (pin "11") (pinfunction "PA1_11") (pintype "bidirectional"))
    )
    (net (code "95") (name "unconnected-(U2-PA4-Pad14)") (class "Default")
      (node (ref "U2") (pin "14") (pinfunction "PA4_14") (pintype "bidirectional"))
    )
    (net (code "96") (name "unconnected-(U2-PA5-Pad15)") (class "Default")
      (node (ref "U2") (pin "15") (pinfunction "PA5_15") (pintype "bidirectional"))
    )
    (net (code "97") (name "unconnected-(U2-PA6-Pad16)") (class "Default")
      (node (ref "U2") (pin "16") (pinfunction "PA6_16") (pintype "bidirectional"))
    )
    (net (code "98") (name "unconnected-(U2-PA7-Pad17)") (class "Default")
      (node (ref "U2") (pin "17") (pinfunction "PA7_17") (pintype "bidirectional"))
    )
    (net (code "99") (name "unconnected-(U2-PA8-Pad29)") (class "Default")
      (node (ref "U2") (pin "29") (pinfunction "PA8_29") (pintype "bidirectional"))
    )
    (net (code "100") (name "unconnected-(U2-PA9-Pad30)") (class "Default")
      (node (ref "U2") (pin "30") (pinfunction "PA9_30") (pintype "bidirectional"))
    )
    (net (code "101") (name "unconnected-(U2-PA10-Pad31)") (class "Default")
      (node (ref "U2") (pin "31") (pinfunction "PA10_31") (pintype "bidirectional"))
    )
    (net (code "102") (name "unconnected-(U2-PA15-Pad38)") (class "Default")
      (node (ref "U2") (pin "38") (pinfunction "PA15_38") (pintype "bidirectional"))
    )
    (net (code "103") (name "unconnected-(U2-PB0-Pad18)") (class "Default")
      (node (ref "U2") (pin "18") (pinfunction "PB0_18") (pintype "bidirectional"))
    )
    (net (code "104") (name "unconnected-(U2-PB1-Pad19)") (class "Default")
      (node (ref "U2") (pin "19") (pinfunction "PB1_19") (pintype "bidirectional"))
    )
    (net (code "105") (name "unconnected-(U2-PB3-Pad39)") (class "Default")
      (node (ref "U2") (pin "39") (pinfunction "PB3_39") (pintype "bidirectional"))
    )
    (net (code "106") (name "unconnected-(U2-PB4-Pad40)") (class "Default")
      (node (ref "U2") (pin "40") (pinfunction "PB4_40") (pintype "bidirectional"))
    )
    (net (code "107") (name "unconnected-(U2-PB5-Pad41)") (class "Default")
      (node (ref "U2") (pin "41") (pinfunction "PB5_41") (pintype "bidirectional"))
    )
    (net (code "108") (name "unconnected-(U2-PB6-Pad42)") (class "Default")
      (node (ref "U2") (pin "42") (pinfunction "PB6_42") (pintype "bidirectional"))
    )
    (net (code "109") (name "unconnected-(U2-PB7-Pad43)") (class "Default")
      (node (ref "U2") (pin "43") (pinfunction "PB7_43") (pintype "bidirectional"))
    )
    (net (code "110") (name "unconnected-(U2-PB8-Pad45)") (class "Default")
      (node (ref "U2") (pin "45") (pinfunction "PB8_45") (pintype "bidirectional"))
    )
    (net (code "111") (name "unconnected-(U2-PB9-Pad46)") (class "Default")
      (node (ref "U2") (pin "46") (pinfunction "PB9_46") (pintype "bidirectional"))
    )
    (net (code "112") (name "unconnected-(U2-PB10-Pad21)") (class "Default")
      (node (ref "U2") (pin "21") (pinfunction "PB10_21") (pintype "bidirectional"))
    )
    (net (code "113") (name "unconnected-(U2-PB11-Pad22)") (class "Default")
      (node (ref "U2") (pin "22") (pinfunction "PB11_22") (pintype "bidirectional"))
    )
    (net (code "114") (name "unconnected-(U2-PB12-Pad25)") (class "Default")
      (node (ref "U2") (pin "25") (pinfunction "PB12_25") (pintype "bidirectional"))
    )
    (net (code "115") (name "unconnected-(U2-PB13-Pad26)") (class "Default")
      (node (ref "U2") (pin "26") (pinfunction "PB13_26") (pintype "bidirectional"))
    )
    (net (code "116") (name "unconnected-(U2-PB14-Pad27)") (class "Default")
      (node (ref "U2") (pin "27") (pinfunction "PB14_27") (pintype "bidirectional"))
    )
    (net (code "117") (name "unconnected-(U2-PB15-Pad28)") (class "Default")
      (node (ref "U2") (pin "28") (pinfunction "PB15_28") (pintype "bidirectional"))
    )
    (net (code "118") (name "unconnected-(U2-PC13-TAMPER-RTC-Pad2)") (class "Default")
      (node (ref "U2") (pin "2") (pinfunction "PC13-TAMPER-RTC_2") (pintype "bidirectional"))
    )
    (net (code "119") (name "unconnected-(U2-PC15-OSC32_OUT-Pad4)") (class "Default")
      (node (ref "U2") (pin "4") (pinfunction "PC15-OSC32_OUT_4") (pintype "bidirectional"))
    )
    (net (code "120") (name "unconnected-(U2-VBAT-Pad1)") (class "Default")
      (node (ref "U2") (pin "1") (pinfunction "VBAT_1") (pintype "passive"))
    )
    (net (code "121") (name "unconnected-(U3-Vout-Pad2)") (class "Default")
      (node (ref "U3") (pin "2") (pinfunction "Vout_2") (pintype "unspecified"))
    )
    (net (code "122") (name "unconnected-(U5-GND{slash}VSS-Pad14)") (class "Default")
      (node (ref "U5") (pin "14") (pinfunction "GND/VSS_14") (pintype "unspecified"))
    )
    (net (code "123") (name "unconnected-(U5-P1.1{slash}T2EX{slash}CAP2{slash}TIN1{slash}VBUS2{slash}AIN0-Pad9)") (class "Default")
      (node (ref "U5") (pin "9") (pinfunction "P1.1/T2EX/CAP2/TIN1/VBUS2/AIN0_9") (pintype "unspecified"))
    )
    (net (code "124") (name "unconnected-(U5-P1.4{slash}T2_{slash}CAP1_{slash}SCS{slash}TIN2{slash}UCC1{slash}AIN1-Pad2)") (class "Default")
      (node (ref "U5") (pin "2") (pinfunction "P1.4/T2_/CAP1_/SCS/TIN2/UCC1/AIN1_2") (pintype "unspecified"))
    )
    (net (code "125") (name "unconnected-(U5-P1.5{slash}MOSI{slash}PWM1{slash}TIN3{slash}UCC2{slash}AIN2-Pad3)") (class "Default")
      (node (ref "U5") (pin "3") (pinfunction "P1.5/MOSI/PWM1/TIN3/UCC2/AIN2_3") (pintype "unspecified"))
    )
    (net (code "126") (name "unconnected-(U5-P1.6{slash}MISO{slash}RXD1{slash}TIN4-Pad4)") (class "Default")
      (node (ref "U5") (pin "4") (pinfunction "P1.6/MISO/RXD1/TIN4_4") (pintype "unspecified"))
    )
    (net (code "127") (name "unconnected-(U5-P1.7{slash}SCK{slash}TXD1{slash}TIN5-Pad5)") (class "Default")
      (node (ref "U5") (pin "5") (pinfunction "P1.7/SCK/TXD1/TIN5_5") (pintype "unspecified"))
    )
    (net (code "128") (name "unconnected-(U5-P3.0{slash}PWM1_{slash}RXD-Pad8)") (class "Default")
      (node (ref "U5") (pin "8") (pinfunction "P3.0/PWM1_/RXD_8") (pintype "unspecified"))
    )
    (net (code "129") (name "unconnected-(U5-P3.1{slash}PWM2_{slash}TXD-Pad7)") (class "Default")
      (node (ref "U5") (pin "7") (pinfunction "P3.1/PWM2_/TXD_7") (pintype "unspecified"))
    )
    (net (code "130") (name "unconnected-(U5-P3.2{slash}TXD1_{slash}INT0{slash}VBUS1{slash}AIN3-Pad1)") (class "Default")
      (node (ref "U5") (pin "1") (pinfunction "P3.2/TXD1_/INT0/VBUS1/AIN3_1") (pintype "unspecified"))
    )
    (net (code "131") (name "unconnected-(U5-P3.3{slash}INT1-Pad10)") (class "Default")
      (node (ref "U5") (pin "10") (pinfunction "P3.3/INT1_10") (pintype "unspecified"))
    )
    (net (code "132") (name "unconnected-(U5-P3.4{slash}PWM2{slash}RXD1_{slash}T0-Pad11)") (class "Default")
      (node (ref "U5") (pin "11") (pinfunction "P3.4/PWM2/RXD1_/T0_11") (pintype "unspecified"))
    )
    (net (code "133") (name "unconnected-(U5-P3.6{slash}UDP-Pad12)") (class "Default")
      (node (ref "U5") (pin "12") (pinfunction "P3.6/UDP_12") (pintype "unspecified"))
    )
    (net (code "134") (name "unconnected-(U5-P3.7{slash}UDM-Pad13)") (class "Default")
      (node (ref "U5") (pin "13") (pinfunction "P3.7/UDM_13") (pintype "unspecified"))
    )
    (net (code "135") (name "unconnected-(U5-RST{slash}T2EX_{slash}CAP2_-Pad6)") (class "Default")
      (node (ref "U5") (pin "6") (pinfunction "RST/T2EX_/CAP2__6") (pintype "unspecified"))
    )
    (net (code "136") (name "unconnected-(U5-V33-Pad16)") (class "Default")
      (node (ref "U5") (pin "16") (pinfunction "V33_16") (pintype "unspecified"))
    )
    (net (code "137") (name "unconnected-(U5-VCC{slash}VDD-Pad15)") (class "Default")
      (node (ref "U5") (pin "15") (pinfunction "VCC/VDD_15") (pintype "unspecified"))
    )
    (net (code "138") (name "unconnected-(U6-3.3V-Pad42)") (class "Default")
      (node (ref "U6") (pin "42") (pinfunction "3.3V_42") (pintype "unspecified"))
    )
    (net (code "139") (name "unconnected-(U6-5V-Pad41)") (class "Default")
      (node (ref "U6") (pin "41") (pinfunction "5V_41") (pintype "unspecified"))
    )
    (net (code "140") (name "unconnected-(U6-39*-Pad39)") (class "Default")
      (node (ref "U6") (pin "39") (pinfunction "39*_39") (pintype "unspecified"))
    )
    (net (code "141") (name "unconnected-(U6-BUTTON-Pad0)") (class "Default")
      (node (ref "U6") (pin "0") (pinfunction "BUTTON_0") (pintype "bidirectional"))
    )
    (net (code "142") (name "unconnected-(U6-GND-Pad40)") (class "Default")
      (node (ref "U6") (pin "40") (pinfunction "GND_40") (pintype "unspecified"))
    )
    (net (code "143") (name "unconnected-(U6-LED-Pad2)") (class "Default")
      (node (ref "U6") (pin "2") (pinfunction "LED_2") (pintype "unspecified"))
    )
    (net (code "144") (name "unconnected-(U6-MISO-Pad19)") (class "Default")
      (node (ref "U6") (pin "19") (pinfunction "MISO_19") (pintype "unspecified"))
    )
    (net (code "145") (name "unconnected-(U6-MOSI-Pad23)") (class "Default")
      (node (ref "U6") (pin "23") (pinfunction "MOSI_23") (pintype "unspecified"))
    )
    (net (code "146") (name "unconnected-(U6-OLED_RST-Pad16)") (class "Default")
      (node (ref "U6") (pin "16") (pinfunction "OLED_RST_16") (pintype "unspecified"))
    )
    (net (code "147") (name "unconnected-(U6-OLED_SCL-Pad15)") (class "Default")
      (node (ref "U6") (pin "15") (pinfunction "OLED_SCL_15") (pintype "unspecified"))
    )
    (net (code "148") (name "unconnected-(U6-OLED_SDA-Pad4)") (class "Default")
      (node (ref "U6") (pin "4") (pinfunction "OLED_SDA_4") (pintype "unspecified"))
    )
    (net (code "149") (name "unconnected-(U6-Pad5)") (class "Default")
      (node (ref "U6") (pin "5") (pinfunction "5_5") (pintype "unspecified"))
    )
    (net (code "150") (name "unconnected-(U6-Pad12)") (class "Default")
      (node (ref "U6") (pin "12") (pinfunction "12_12") (pintype "unspecified"))
    )
    (net (code "151") (name "unconnected-(U6-Pad13)") (class "Default")
      (node (ref "U6") (pin "13") (pinfunction "13_13") (pintype "unspecified"))
    )
    (net (code "152") (name "unconnected-(U6-Pad14)") (class "Default")
      (node (ref "U6") (pin "14") (pinfunction "14_14") (pintype "unspecified"))
    )
    (net (code "153") (name "unconnected-(U6-Pad17)") (class "Default")
      (node (ref "U6") (pin "17") (pinfunction "17_17") (pintype "unspecified"))
    )
    (net (code "154") (name "unconnected-(U6-Pad25)") (class "Default")
      (node (ref "U6") (pin "25") (pinfunction "25_25") (pintype "unspecified"))
    )
    (net (code "155") (name "unconnected-(U6-Pad26)") (class "Default")
      (node (ref "U6") (pin "26") (pinfunction "26_26") (pintype "unspecified"))
    )
    (net (code "156") (name "unconnected-(U6-Pad27)") (class "Default")
      (node (ref "U6") (pin "27") (pinfunction "27_27") (pintype "unspecified"))
    )
    (net (code "157") (name "unconnected-(U6-Pad32)") (class "Default")
      (node (ref "U6") (pin "32") (pinfunction "32_32") (pintype "unspecified"))
    )
    (net (code "158") (name "unconnected-(U6-Pad33)") (class "Default")
      (node (ref "U6") (pin "33") (pinfunction "33_33") (pintype "unspecified"))
    )
    (net (code "159") (name "unconnected-(U6-Pad34)") (class "Default")
      (node (ref "U6") (pin "34") (pinfunction "34_34") (pintype "unspecified"))
    )
    (net (code "160") (name "unconnected-(U6-Pad35)") (class "Default")
      (node (ref "U6") (pin "35") (pinfunction "35_35") (pintype "unspecified"))
    )
    (net (code "161") (name "unconnected-(U6-Pad36)") (class "Default")
      (node (ref "U6") (pin "36") (pinfunction "36_36") (pintype "unspecified"))
    )
    (net (code "162") (name "unconnected-(U6-Pad37)") (class "Default")
      (node (ref "U6") (pin "37") (pinfunction "37_37") (pintype "unspecified"))
    )
    (net (code "163") (name "unconnected-(U6-Pad38)") (class "Default")
      (node (ref "U6") (pin "38") (pinfunction "38_38") (pintype "unspecified"))
    )
    (net (code "164") (name "unconnected-(U6-RST-Pad44)") (class "Default")
      (node (ref "U6") (pin "44") (pinfunction "RST_44") (pintype "unspecified"))
    )
    (net (code "165") (name "unconnected-(U6-RX-Pad3)") (class "Default")
      (node (ref "U6") (pin "3") (pinfunction "RX_3") (pintype "unspecified"))
    )
    (net (code "166") (name "unconnected-(U6-SCK-Pad18)") (class "Default")
      (node (ref "U6") (pin "18") (pinfunction "SCK_18") (pintype "unspecified"))
    )
    (net (code "167") (name "unconnected-(U6-SCL-Pad22)") (class "Default")
      (node (ref "U6") (pin "22") (pinfunction "SCL_22") (pintype "unspecified"))
    )
    (net (code "168") (name "unconnected-(U6-SDA-Pad21)") (class "Default")
      (node (ref "U6") (pin "21") (pinfunction "SDA_21") (pintype "unspecified"))
    )
    (net (code "169") (name "unconnected-(U6-TX-Pad1)") (class "Default")
      (node (ref "U6") (pin "1") (pinfunction "TX_1") (pintype "unspecified"))
    )
    (net (code "170") (name "unconnected-(U7-39*-Pad39)") (class "Default")
      (node (ref "U7") (pin "39") (pinfunction "39*_39") (pintype "unspecified"))
    )
    (net (code "171") (name "unconnected-(U7-BUTTON-Pad0)") (class "Default")
      (node (ref "U7") (pin "0") (pinfunction "BUTTON_0") (pintype "bidirectional"))
    )
    (net (code "172") (name "unconnected-(U7-LED-Pad2)") (class "Default")
      (node (ref "U7") (pin "2") (pinfunction "LED_2") (pintype "unspecified"))
    )
    (net (code "173") (name "unconnected-(U7-OLED_RST-Pad16)") (class "Default")
      (node (ref "U7") (pin "16") (pinfunction "OLED_RST_16") (pintype "unspecified"))
    )
    (net (code "174") (name "unconnected-(U7-OLED_SCL-Pad15)") (class "Default")
      (node (ref "U7") (pin "15") (pinfunction "OLED_SCL_15") (pintype "unspecified"))
    )
    (net (code "175") (name "unconnected-(U7-OLED_SDA-Pad4)") (class "Default")
      (node (ref "U7") (pin "4") (pinfunction "OLED_SDA_4") (pintype "unspecified"))
    )
    (net (code "176") (name "unconnected-(U7-Pad12)") (class "Default")
      (node (ref "U7") (pin "12") (pinfunction "12_12") (pintype "unspecified"))
    )
    (net (code "177") (name "unconnected-(U7-Pad13)") (class "Default")
      (node (ref "U7") (pin "13") (pinfunction "13_13") (pintype "unspecified"))
    )
    (net (code "178") (name "unconnected-(U7-Pad14)") (class "Default")
      (node (ref "U7") (pin "14") (pinfunction "14_14") (pintype "unspecified"))
    )
    (net (code "179") (name "unconnected-(U7-Pad25)") (class "Default")
      (node (ref "U7") (pin "25") (pinfunction "25_25") (pintype "unspecified"))
    )
    (net (code "180") (name "unconnected-(U7-Pad26)") (class "Default")
      (node (ref "U7") (pin "26") (pinfunction "26_26") (pintype "unspecified"))
    )
    (net (code "181") (name "unconnected-(U7-Pad27)") (class "Default")
      (node (ref "U7") (pin "27") (pinfunction "27_27") (pintype "unspecified"))
    )
    (net (code "182") (name "unconnected-(U7-Pad34)") (class "Default")
      (node (ref "U7") (pin "34") (pinfunction "34_34") (pintype "unspecified"))
    )
    (net (code "183") (name "unconnected-(U7-RST-Pad44)") (class "Default")
      (node (ref "U7") (pin "44") (pinfunction "RST_44") (pintype "unspecified"))
    )
    (net (code "184") (name "unconnected-(U7-SCL-Pad22)") (class "Default")
      (node (ref "U7") (pin "22") (pinfunction "SCL_22") (pintype "unspecified"))
    )
    (net (code "185") (name "unconnected-(U7-SDA-Pad21)") (class "Default")
      (node (ref "U7") (pin "21") (pinfunction "SDA_21") (pintype "unspecified"))
    )
    (net (code "186") (name "unconnected-(U8-P1.1{slash}T2EX{slash}CAP2{slash}TIN1{slash}VBUS2{slash}AIN0-Pad9)") (class "Default")
      (node (ref "U8") (pin "9") (pinfunction "P1.1/T2EX/CAP2/TIN1/VBUS2/AIN0_9") (pintype "unspecified+no_connect"))
    )
    (net (code "187") (name "unconnected-(U8-P1.4{slash}T2_{slash}CAP1_{slash}SCS{slash}TIN2{slash}UCC1{slash}AIN1-Pad2)") (class "Default")
      (node (ref "U8") (pin "2") (pinfunction "P1.4/T2_/CAP1_/SCS/TIN2/UCC1/AIN1_2") (pintype "unspecified+no_connect"))
    )
    (net (code "188") (name "unconnected-(U8-P1.5{slash}MOSI{slash}PWM1{slash}TIN3{slash}UCC2{slash}AIN2-Pad3)") (class "Default")
      (node (ref "U8") (pin "3") (pinfunction "P1.5/MOSI/PWM1/TIN3/UCC2/AIN2_3") (pintype "unspecified+no_connect"))
    )
    (net (code "189") (name "unconnected-(U8-P3.2{slash}TXD1_{slash}INT0{slash}VBUS1{slash}AIN3-Pad1)") (class "Default")
      (node (ref "U8") (pin "1") (pinfunction "P3.2/TXD1_/INT0/VBUS1/AIN3_1") (pintype "unspecified+no_connect"))
    )
    (net (code "190") (name "unconnected-(U8-P3.3{slash}INT1-Pad10)") (class "Default")
      (node (ref "U8") (pin "10") (pinfunction "P3.3/INT1_10") (pintype "unspecified+no_connect"))
    )
    (net (code "191") (name "unconnected-(U8-P3.4{slash}PWM2{slash}RXD1_{slash}T0-Pad11)") (class "Default")
      (node (ref "U8") (pin "11") (pinfunction "P3.4/PWM2/RXD1_/T0_11") (pintype "unspecified+no_connect"))
    )
  )
)
